# MCU.net
KiCad netlist of a schematic drawn in Altium Designer
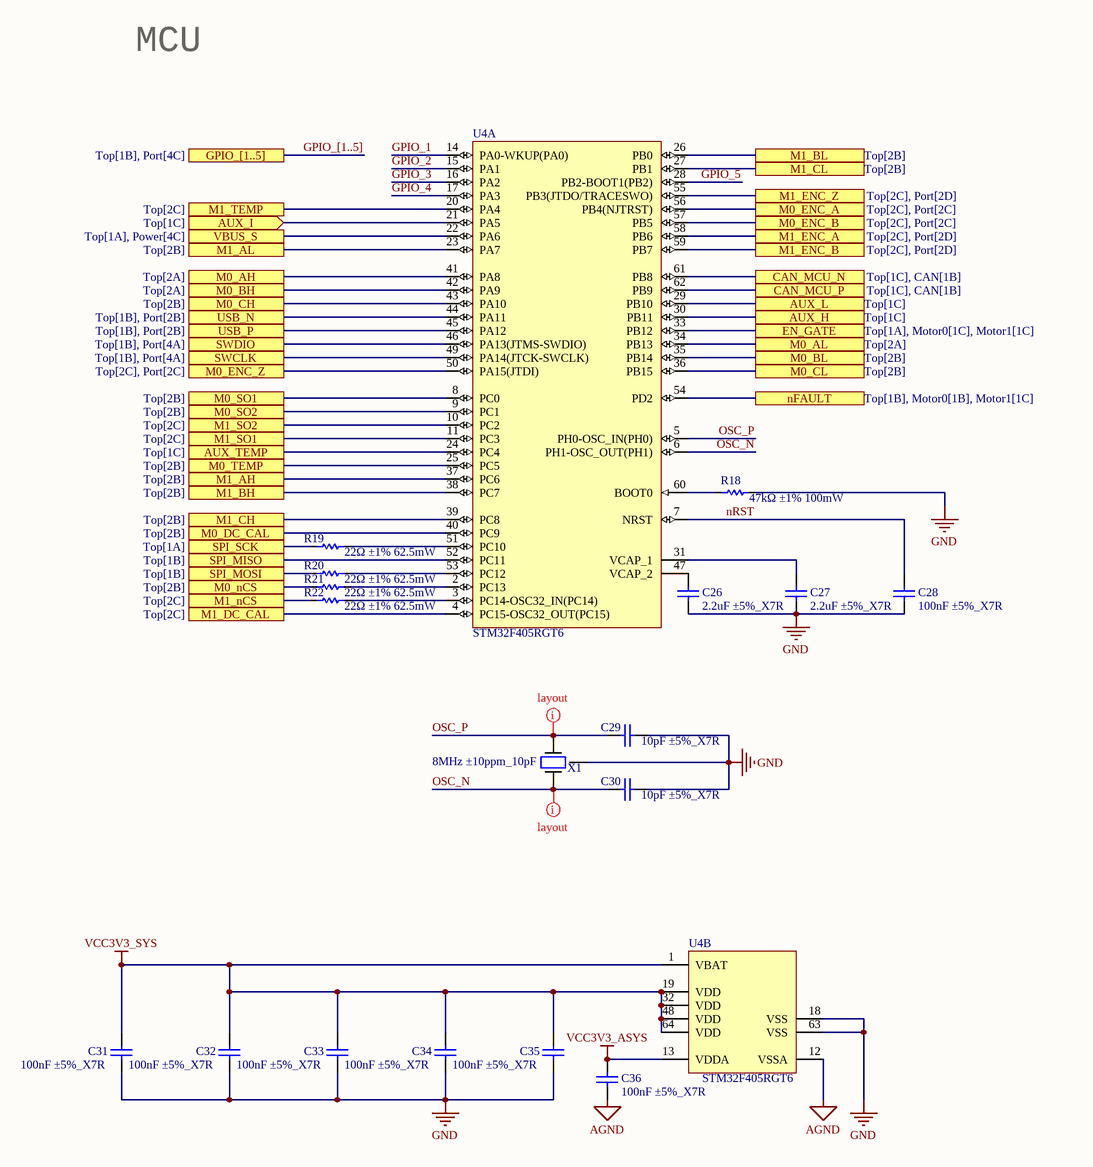
[diagram p0: MCU.SchDoc]

(export (version "E")
  (design (tool "Eeschema 10.0.6"))
  (components
    (comp (ref "C26")
      (value "2.2uF ±5%_X7R")
      (footprint "WCAP-CSGP_0603_L1.6W0.8H0.8_Reflow")
      (description "Capacitor")
      (fields (field (name "PUBLISHER") "Altium Limited"))
      (libsource (lib "Component") (part "Cap"))
    )
    (comp (ref "C27")
      (value "2.2uF ±5%_X7R")
      (footprint "WCAP-CSGP_0603_L1.6W0.8H0.8_Reflow")
      (description "Capacitor")
      (fields (field (name "PUBLISHER") "Altium Limited"))
      (libsource (lib "Component") (part "Cap"))
    )
    (comp (ref "C28")
      (value "100nF ±5%_X7R")
      (footprint "WCAP-CSGP_0402_L1W0.5H0.5")
      (description "Capacitor")
      (fields (field (name "PUBLISHER") "Altium Limited"))
      (libsource (lib "Component") (part "Cap"))
    )
    (comp (ref "C29")
      (value "10pF ±5%_X7R")
      (footprint "WCAP-CSGP_0402_L1W0.5H0.5")
      (description "Capacitor")
      (fields (field (name "PUBLISHER") "Altium Limited"))
      (libsource (lib "Component") (part "Cap"))
    )
    (comp (ref "C30")
      (value "10pF ±5%_X7R")
      (footprint "WCAP-CSGP_0402_L1W0.5H0.5")
      (description "Capacitor")
      (fields (field (name "PUBLISHER") "Altium Limited"))
      (libsource (lib "Component") (part "Cap"))
    )
    (comp (ref "C31")
      (value "100nF ±5%_X7R")
      (footprint "WCAP-CSGP_0402_L1W0.5H0.5")
      (description "Capacitor")
      (fields (field (name "PUBLISHER") "Altium Limited"))
      (libsource (lib "Component") (part "Cap"))
    )
    (comp (ref "C32")
      (value "100nF ±5%_X7R")
      (footprint "WCAP-CSGP_0402_L1W0.5H0.5")
      (description "Capacitor")
      (fields (field (name "PUBLISHER") "Altium Limited"))
      (libsource (lib "Component") (part "Cap"))
    )
    (comp (ref "C33")
      (value "100nF ±5%_X7R")
      (footprint "WCAP-CSGP_0402_L1W0.5H0.5")
      (description "Capacitor")
      (fields (field (name "PUBLISHER") "Altium Limited"))
      (libsource (lib "Component") (part "Cap"))
    )
    (comp (ref "C34")
      (value "100nF ±5%_X7R")
      (footprint "WCAP-CSGP_0402_L1W0.5H0.5")
      (description "Capacitor")
      (fields (field (name "PUBLISHER") "Altium Limited"))
      (libsource (lib "Component") (part "Cap"))
    )
    (comp (ref "C35")
      (value "100nF ±5%_X7R")
      (footprint "WCAP-CSGP_0402_L1W0.5H0.5")
      (description "Capacitor")
      (fields (field (name "PUBLISHER") "Altium Limited"))
      (libsource (lib "Component") (part "Cap"))
    )
    (comp (ref "C36")
      (value "100nF ±5%_X7R")
      (footprint "WCAP-CSGP_0402_L1W0.5H0.5")
      (description "Capacitor")
      (fields (field (name "PUBLISHER") "Altium Limited"))
      (libsource (lib "Component") (part "Cap"))
    )
    (comp (ref "R18")
      (value "47kΩ ±1% 100mW")
      (footprint "WRIS-KSKE_0402")
      (description "Resistor")
      (fields (field (name "PUBLISHER") "Altium Limited"))
      (libsource (lib "Component") (part "Res"))
    )
    (comp (ref "R19")
      (value "22Ω ±1% 62.5mW")
      (footprint "WRIS-KSKE_0402")
      (description "Resistor")
      (fields (field (name "PUBLISHER") "Altium Limited"))
      (libsource (lib "Component") (part "Res"))
    )
    (comp (ref "R20")
      (value "22Ω ±1% 62.5mW")
      (footprint "WRIS-KSKE_0402")
      (description "Resistor")
      (fields (field (name "PUBLISHER") "Altium Limited"))
      (libsource (lib "Component") (part "Res"))
    )
    (comp (ref "R21")
      (value "22Ω ±1% 62.5mW")
      (footprint "WRIS-KSKE_0402")
      (description "Resistor")
      (fields (field (name "PUBLISHER") "Altium Limited"))
      (libsource (lib "Component") (part "Res"))
    )
    (comp (ref "R22")
      (value "22Ω ±1% 62.5mW")
      (footprint "WRIS-KSKE_0402")
      (description "Resistor")
      (fields (field (name "PUBLISHER") "Altium Limited"))
      (libsource (lib "Component") (part "Res"))
    )
    (comp (ref "U4")
      (value "STM32F405RGT6")
      (footprint "STM-LQFP64_N")
      (fields (field (name "MANUFACTURER") "STMicroelectronics"))
      (libsource (lib "STMicroelectronics STM32 F4") (part "STM32F405RGT6"))
    )
    (comp (ref "X1")
      (value "8MHz ±10ppm_10pF")
      (footprint "CRYSTAL_3225")
      (description "Crystal 8MHz ±10ppm 10pF 200 Ohm -10°C ~ 60°C Surface Mount 4-SMD, No Lead (DFN, LCC)")
      (fields
        (field (name "MANUFACTURER") "Abracon LLC")
        (field (name "MANUFACTURER PART NUMBER") "ABM3B-8.000MHZ-10-1-U-T")
      )
      (libsource (lib "Component") (part "CRYSTAL"))
    )
  )
  (nets
    (net (code "1") (name "/AUX_H") (class "Default")
      (node (ref "U4") (pin "30") (pinfunction "PB11_30") (pintype "bidirectional"))
    )
    (net (code "2") (name "/AUX_I") (class "Default")
      (node (ref "U4") (pin "21") (pinfunction "PA5_21") (pintype "bidirectional"))
    )
    (net (code "3") (name "/AUX_L") (class "Default")
      (node (ref "U4") (pin "29") (pinfunction "PB10_29") (pintype "bidirectional"))
    )
    (net (code "4") (name "/AUX_TEMP") (class "Default")
      (node (ref "U4") (pin "24") (pinfunction "PC4_24") (pintype "bidirectional"))
    )
    (net (code "5") (name "/CAN_MCU_N") (class "Default")
      (node (ref "U4") (pin "61") (pinfunction "PB8_61") (pintype "bidirectional"))
    )
    (net (code "6") (name "/CAN_MCU_P") (class "Default")
      (node (ref "U4") (pin "62") (pinfunction "PB9_62") (pintype "bidirectional"))
    )
    (net (code "7") (name "/EN_GATE") (class "Default")
      (node (ref "U4") (pin "33") (pinfunction "PB12_33") (pintype "bidirectional"))
    )
    (net (code "8") (name "/GPIO_1") (class "Default")
      (node (ref "U4") (pin "14") (pinfunction "PA0-WKUP(PA0)_14") (pintype "bidirectional"))
    )
    (net (code "9") (name "/GPIO_2") (class "Default")
      (node (ref "U4") (pin "15") (pinfunction "PA1_15") (pintype "bidirectional"))
    )
    (net (code "10") (name "/GPIO_3") (class "Default")
      (node (ref "U4") (pin "16") (pinfunction "PA2_16") (pintype "bidirectional"))
    )
    (net (code "11") (name "/GPIO_4") (class "Default")
      (node (ref "U4") (pin "17") (pinfunction "PA3_17") (pintype "bidirectional"))
    )
    (net (code "12") (name "/GPIO_5") (class "Default")
      (node (ref "U4") (pin "28") (pinfunction "PB2-BOOT1(PB2)_28") (pintype "bidirectional"))
    )
    (net (code "14") (name "/M0_AH") (class "Default")
      (node (ref "U4") (pin "41") (pinfunction "PA8_41") (pintype "bidirectional"))
    )
    (net (code "15") (name "/M0_AL") (class "Default")
      (node (ref "U4") (pin "34") (pinfunction "PB13_34") (pintype "bidirectional"))
    )
    (net (code "16") (name "/M0_BH") (class "Default")
      (node (ref "U4") (pin "42") (pinfunction "PA9_42") (pintype "bidirectional"))
    )
    (net (code "17") (name "/M0_BL") (class "Default")
      (node (ref "U4") (pin "35") (pinfunction "PB14_35") (pintype "bidirectional"))
    )
    (net (code "18") (name "/M0_CH") (class "Default")
      (node (ref "U4") (pin "43") (pinfunction "PA10_43") (pintype "bidirectional"))
    )
    (net (code "19") (name "/M0_CL") (class "Default")
      (node (ref "U4") (pin "36") (pinfunction "PB15_36") (pintype "bidirectional"))
    )
    (net (code "20") (name "/M0_DC_CAL") (class "Default")
      (node (ref "U4") (pin "40") (pinfunction "PC9_40") (pintype "bidirectional"))
    )
    (net (code "21") (name "/M0_ENC_A") (class "Default")
      (node (ref "U4") (pin "56") (pinfunction "PB4(NJTRST)_56") (pintype "bidirectional"))
    )
    (net (code "22") (name "/M0_ENC_B") (class "Default")
      (node (ref "U4") (pin "57") (pinfunction "PB5_57") (pintype "bidirectional"))
    )
    (net (code "23") (name "/M0_ENC_Z") (class "Default")
      (node (ref "U4") (pin "50") (pinfunction "PA15(JTDI)_50") (pintype "bidirectional"))
    )
    (net (code "24") (name "/M0_SO1") (class "Default")
      (node (ref "U4") (pin "8") (pinfunction "PC0_8") (pintype "bidirectional"))
    )
    (net (code "25") (name "/M0_SO2") (class "Default")
      (node (ref "U4") (pin "9") (pinfunction "PC1_9") (pintype "bidirectional"))
    )
    (net (code "26") (name "/M0_TEMP") (class "Default")
      (node (ref "U4") (pin "25") (pinfunction "PC5_25") (pintype "bidirectional"))
    )
    (net (code "27") (name "/M0_nCS") (class "Default")
      (node (ref "R21") (pin "1") (pinfunction "1_1") (pintype "passive"))
    )
    (net (code "28") (name "/M1_AH") (class "Default")
      (node (ref "U4") (pin "37") (pinfunction "PC6_37") (pintype "bidirectional"))
    )
    (net (code "29") (name "/M1_AL") (class "Default")
      (node (ref "U4") (pin "23") (pinfunction "PA7_23") (pintype "bidirectional"))
    )
    (net (code "30") (name "/M1_BH") (class "Default")
      (node (ref "U4") (pin "38") (pinfunction "PC7_38") (pintype "bidirectional"))
    )
    (net (code "31") (name "/M1_BL") (class "Default")
      (node (ref "U4") (pin "26") (pinfunction "PB0_26") (pintype "bidirectional"))
    )
    (net (code "32") (name "/M1_CH") (class "Default")
      (node (ref "U4") (pin "39") (pinfunction "PC8_39") (pintype "bidirectional"))
    )
    (net (code "33") (name "/M1_CL") (class "Default")
      (node (ref "U4") (pin "27") (pinfunction "PB1_27") (pintype "bidirectional"))
    )
    (net (code "34") (name "/M1_DC_CAL") (class "Default")
      (node (ref "U4") (pin "4") (pinfunction "PC15-OSC32_OUT(PC15)_4") (pintype "bidirectional"))
    )
    (net (code "35") (name "/M1_ENC_A") (class "Default")
      (node (ref "U4") (pin "58") (pinfunction "PB6_58") (pintype "bidirectional"))
    )
    (net (code "36") (name "/M1_ENC_B") (class "Default")
      (node (ref "U4") (pin "59") (pinfunction "PB7_59") (pintype "bidirectional"))
    )
    (net (code "37") (name "/M1_ENC_Z") (class "Default")
      (node (ref "U4") (pin "55") (pinfunction "PB3(JTDO/TRACESWO)_55") (pintype "bidirectional"))
    )
    (net (code "38") (name "/M1_SO1") (class "Default")
      (node (ref "U4") (pin "11") (pinfunction "PC3_11") (pintype "bidirectional"))
    )
    (net (code "39") (name "/M1_SO2") (class "Default")
      (node (ref "U4") (pin "10") (pinfunction "PC2_10") (pintype "bidirectional"))
    )
    (net (code "40") (name "/M1_TEMP") (class "Default")
      (node (ref "U4") (pin "20") (pinfunction "PA4_20") (pintype "bidirectional"))
    )
    (net (code "41") (name "/M1_nCS") (class "Default")
      (node (ref "R22") (pin "1") (pinfunction "1_1") (pintype "passive"))
    )
    (net (code "42") (name "/OSC_N") (class "Default")
      (node (ref "C30") (pin "1") (pinfunction "1_1") (pintype "passive"))
      (node (ref "U4") (pin "6") (pinfunction "PH1-OSC_OUT(PH1)_6") (pintype "bidirectional"))
      (node (ref "X1") (pin "1") (pintype "passive"))
    )
    (net (code "43") (name "/OSC_P") (class "Default")
      (node (ref "C29") (pin "1") (pinfunction "1_1") (pintype "passive"))
      (node (ref "U4") (pin "5") (pinfunction "PH0-OSC_IN(PH0)_5") (pintype "bidirectional"))
      (node (ref "X1") (pin "3") (pintype "passive"))
    )
    (net (code "44") (name "/SPI_MISO") (class "Default")
      (node (ref "U4") (pin "52") (pinfunction "PC11_52") (pintype "bidirectional"))
    )
    (net (code "45") (name "/SPI_MOSI") (class "Default")
      (node (ref "R20") (pin "1") (pinfunction "1_1") (pintype "passive"))
    )
    (net (code "46") (name "/SPI_SCK") (class "Default")
      (node (ref "R19") (pin "1") (pinfunction "1_1") (pintype "passive"))
    )
    (net (code "47") (name "/SWCLK") (class "Default")
      (node (ref "U4") (pin "49") (pinfunction "PA14(JTCK-SWCLK)_49") (pintype "bidirectional"))
    )
    (net (code "48") (name "/SWDIO") (class "Default")
      (node (ref "U4") (pin "46") (pinfunction "PA13(JTMS-SWDIO)_46") (pintype "bidirectional"))
    )
    (net (code "49") (name "/USB_N") (class "Default")
      (node (ref "U4") (pin "44") (pinfunction "PA11_44") (pintype "bidirectional"))
    )
    (net (code "50") (name "/USB_P") (class "Default")
      (node (ref "U4") (pin "45") (pinfunction "PA12_45") (pintype "bidirectional"))
    )
    (net (code "51") (name "/VBUS_S") (class "Default")
      (node (ref "U4") (pin "22") (pinfunction "PA6_22") (pintype "bidirectional"))
    )
    (net (code "52") (name "/nFAULT") (class "Default")
      (node (ref "U4") (pin "54") (pinfunction "PD2_54") (pintype "bidirectional"))
    )
    (net (code "53") (name "/nRST") (class "Default")
      (node (ref "C28") (pin "2") (pinfunction "2_2") (pintype "passive"))
      (node (ref "U4") (pin "7") (pinfunction "NRST_7") (pintype "bidirectional"))
    )
    (net (code "54") (name "AGND") (class "Default")
      (node (ref "C36") (pin "1") (pinfunction "1_1") (pintype "passive"))
      (node (ref "U4") (pin "12") (pinfunction "VSSA_12") (pintype "power_in"))
    )
    (net (code "55") (name "GND") (class "Default")
      (node (ref "C26") (pin "1") (pinfunction "1_1") (pintype "passive"))
      (node (ref "C27") (pin "1") (pinfunction "1_1") (pintype "passive"))
      (node (ref "C28") (pin "1") (pinfunction "1_1") (pintype "passive"))
      (node (ref "C29") (pin "2") (pinfunction "2_2") (pintype "passive"))
      (node (ref "C30") (pin "2") (pinfunction "2_2") (pintype "passive"))
      (node (ref "C31") (pin "1") (pinfunction "1_1") (pintype "passive"))
      (node (ref "C32") (pin "1") (pinfunction "1_1") (pintype "passive"))
      (node (ref "C33") (pin "1") (pinfunction "1_1") (pintype "passive"))
      (node (ref "C34") (pin "1") (pinfunction "1_1") (pintype "passive"))
      (node (ref "C35") (pin "1") (pinfunction "1_1") (pintype "passive"))
      (node (ref "R18") (pin "2") (pinfunction "2_2") (pintype "passive"))
      (node (ref "U4") (pin "18") (pinfunction "VSS_18") (pintype "power_in"))
      (node (ref "U4") (pin "63") (pinfunction "VSS_63") (pintype "power_in"))
      (node (ref "X1") (pin "G") (pintype "passive"))
    )
    (net (code "56") (name "Net-(U4A-BOOT0)") (class "Default")
      (node (ref "R18") (pin "1") (pinfunction "1_1") (pintype "passive"))
      (node (ref "U4") (pin "60") (pinfunction "BOOT0_60") (pintype "input"))
    )
    (net (code "57") (name "Net-(U4A-PC10)") (class "Default")
      (node (ref "R19") (pin "2") (pinfunction "2_2") (pintype "passive"))
      (node (ref "U4") (pin "51") (pinfunction "PC10_51") (pintype "bidirectional"))
    )
    (net (code "58") (name "Net-(U4A-PC12)") (class "Default")
      (node (ref "R20") (pin "2") (pinfunction "2_2") (pintype "passive"))
      (node (ref "U4") (pin "53") (pinfunction "PC12_53") (pintype "bidirectional"))
    )
    (net (code "59") (name "Net-(U4A-PC13)") (class "Default")
      (node (ref "R21") (pin "2") (pinfunction "2_2") (pintype "passive"))
      (node (ref "U4") (pin "2") (pinfunction "PC13_2") (pintype "bidirectional"))
    )
    (net (code "60") (name "Net-(U4A-PC14-OSC32_IN(PC14))") (class "Default")
      (node (ref "R22") (pin "2") (pinfunction "2_2") (pintype "passive"))
      (node (ref "U4") (pin "3") (pinfunction "PC14-OSC32_IN(PC14)_3") (pintype "bidirectional"))
    )
    (net (code "61") (name "Net-(U4A-VCAP_1)") (class "Default")
      (node (ref "C27") (pin "2") (pinfunction "2_2") (pintype "passive"))
      (node (ref "U4") (pin "31") (pinfunction "VCAP_1_31") (pintype "power_in"))
    )
    (net (code "62") (name "Net-(U4A-VCAP_2)") (class "Default")
      (node (ref "C26") (pin "2") (pinfunction "2_2") (pintype "passive"))
      (node (ref "U4") (pin "47") (pinfunction "VCAP_2_47") (pintype "power_in"))
    )
    (net (code "63") (name "VCC3V3_ASYS") (class "Default")
      (node (ref "C36") (pin "2") (pinfunction "2_2") (pintype "passive"))
      (node (ref "U4") (pin "13") (pinfunction "VDDA_13") (pintype "power_in"))
    )
    (net (code "64") (name "VCC3V3_SYS") (class "Default")
      (node (ref "C31") (pin "2") (pinfunction "2_2") (pintype "passive"))
      (node (ref "C32") (pin "2") (pinfunction "2_2") (pintype "passive"))
      (node (ref "C33") (pin "2") (pinfunction "2_2") (pintype "passive"))
      (node (ref "C34") (pin "2") (pinfunction "2_2") (pintype "passive"))
      (node (ref "C35") (pin "2") (pinfunction "2_2") (pintype "passive"))
      (node (ref "U4") (pin "1") (pinfunction "VBAT_1") (pintype "power_in"))
      (node (ref "U4") (pin "19") (pinfunction "VDD_19") (pintype "power_in"))
      (node (ref "U4") (pin "32") (pinfunction "VDD_32") (pintype "power_in"))
      (node (ref "U4") (pin "48") (pinfunction "VDD_48") (pintype "power_in"))
      (node (ref "U4") (pin "64") (pinfunction "VDD_64") (pintype "power_in"))
    )
  )
)
